# imu-pcb.net
KiCad netlist of a schematic drawn in Altium Designer
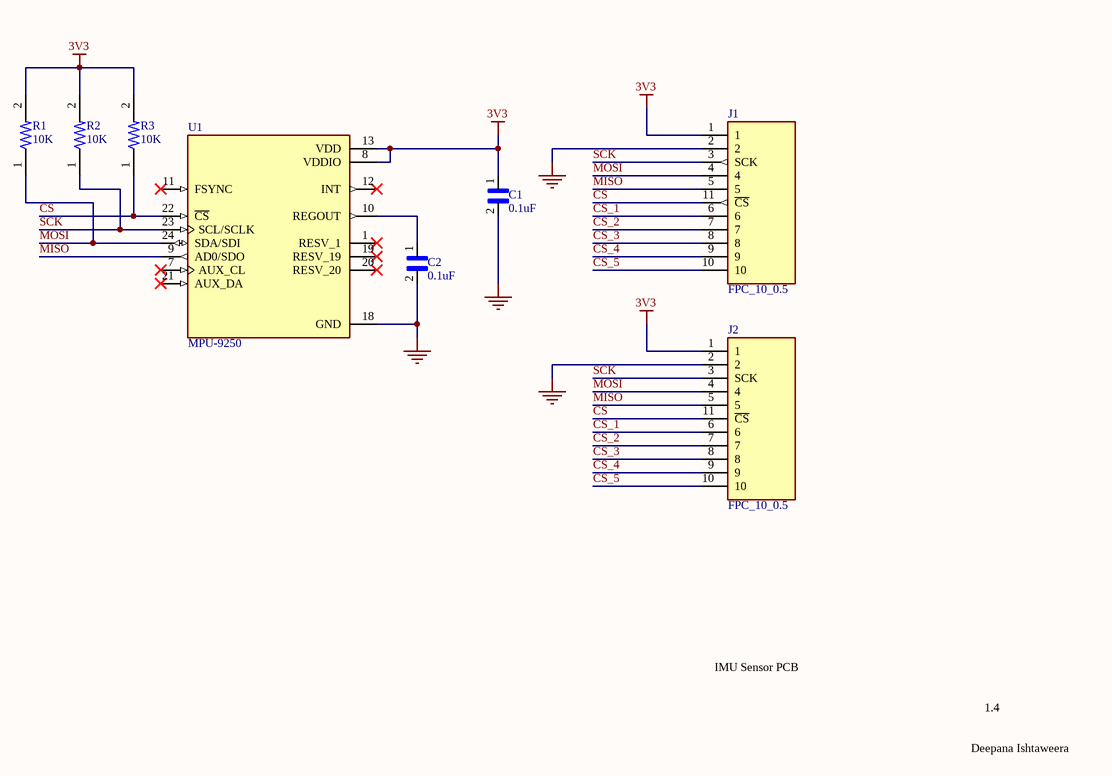
[diagram p0: imu-pcb.SchDoc]

(export (version "E")
  (design (tool "Eeschema 10.0.6"))
  (components
    (comp (ref "C1")
      (value "0.1uF")
      (footprint "CAPC1608X87N")
      (description "10000pF Â±10% 50V Ceramic Capacitor X7R 0603 (1608 Metric)")
      (fields (field (name "MF") "Walsin Technology") (field (name "MP") "0603B103K500CT"))
      (libsource (lib "imu-pcb-lib") (part "0603B103K500CT"))
    )
    (comp (ref "C2")
      (value "0.1uF")
      (footprint "CAPC1608X87N")
      (description "10000pF Â±10% 50V Ceramic Capacitor X7R 0603 (1608 Metric)")
      (fields (field (name "MF") "Walsin Technology") (field (name "MP") "0603B103K500CT"))
      (libsource (lib "imu-pcb-lib") (part "0603B103K500CT"))
    )
    (comp (ref "J1")
      (value "FPC_10_0.5")
      (footprint "FPC_10_0.5")
      (description "6 Position FPC Connector Contacts, Bottom 0.020 (0.50mm) Surface Mount, Right Angle")
      (fields (field (name "MP") "1734592-6") (field (name "MF") "TE Connectivity"))
      (libsource (lib "imu-pcb-lib") (part "FPC_10_0.5"))
    )
    (comp (ref "J2")
      (value "FPC_10_0.5")
      (footprint "FPC_10_0.5_1")
      (description "6 Position FPC Connector Contacts, Bottom 0.020 (0.50mm) Surface Mount, Right Angle")
      (fields (field (name "MP") "1734592-6") (field (name "MF") "TE Connectivity"))
      (libsource (lib "imu-pcb-lib") (part "FPC_10_0.5_1"))
    )
    (comp (ref "R1")
      (value "10K")
      (footprint "RESC1608X50N")
      (description "RES SMD 10 OHM 0.1% 1/16W 0603")
      (fields (field (name "MF") "TE Connectivity") (field (name "MP") "8-1614350-7"))
      (libsource (lib "imu-pcb-lib") (part "RES-0603"))
    )
    (comp (ref "R2")
      (value "10K")
      (footprint "RESC1608X50N")
      (description "RES SMD 10 OHM 0.1% 1/16W 0603")
      (fields (field (name "MF") "TE Connectivity") (field (name "MP") "8-1614350-7"))
      (libsource (lib "imu-pcb-lib") (part "RES-0603"))
    )
    (comp (ref "R3")
      (value "10K")
      (footprint "RESC1608X50N")
      (description "RES SMD 10 OHM 0.1% 1/16W 0603")
      (fields (field (name "MF") "TE Connectivity") (field (name "MP") "8-1614350-7"))
      (libsource (lib "imu-pcb-lib") (part "RES-0603"))
    )
    (comp (ref "U1")
      (value "MPU-9250")
      (footprint "QFN40P300X300X105-24N")
      (description "Accelerometer, Gyroscope, Magnetometer, 9 Axis Sensor IÂ²C, SPI Output")
      (fields (field (name "MF") "TDK InvenSense"))
      (libsource (lib "imu-pcb-lib") (part "MPU-9250"))
    )
  )
  (nets
    (net (code "1") (name "/CS") (class "Default")
      (node (ref "J1") (pin "11") (pinfunction "~{CS}_11") (pintype "output"))
      (node (ref "J2") (pin "11") (pinfunction "~{CS}_11") (pintype "passive"))
      (node (ref "R3") (pin "1") (pinfunction "1_1") (pintype "passive"))
      (node (ref "U1") (pin "22") (pinfunction "~{CS}_22") (pintype "input"))
    )
    (net (code "2") (name "/CS_1") (class "Default")
      (node (ref "J1") (pin "6") (pinfunction "6_6") (pintype "passive"))
      (node (ref "J2") (pin "6") (pinfunction "6_6") (pintype "passive"))
    )
    (net (code "3") (name "/CS_2") (class "Default")
      (node (ref "J1") (pin "7") (pinfunction "7_7") (pintype "passive"))
      (node (ref "J2") (pin "7") (pinfunction "7_7") (pintype "passive"))
    )
    (net (code "4") (name "/CS_3") (class "Default")
      (node (ref "J1") (pin "8") (pinfunction "8_8") (pintype "passive"))
      (node (ref "J2") (pin "8") (pinfunction "8_8") (pintype "passive"))
    )
    (net (code "5") (name "/CS_4") (class "Default")
      (node (ref "J1") (pin "9") (pinfunction "9_9") (pintype "passive"))
      (node (ref "J2") (pin "9") (pinfunction "9_9") (pintype "passive"))
    )
    (net (code "6") (name "/CS_5") (class "Default")
      (node (ref "J1") (pin "10") (pinfunction "10_10") (pintype "passive"))
      (node (ref "J2") (pin "10") (pinfunction "10_10") (pintype "passive"))
    )
    (net (code "7") (name "/MISO") (class "Default")
      (node (ref "J1") (pin "5") (pinfunction "5_5") (pintype "passive"))
      (node (ref "J2") (pin "5") (pinfunction "5_5") (pintype "passive"))
      (node (ref "U1") (pin "9") (pinfunction "AD0/SDO_9") (pintype "output"))
    )
    (net (code "8") (name "/MOSI") (class "Default")
      (node (ref "J1") (pin "4") (pinfunction "4_4") (pintype "passive"))
      (node (ref "J2") (pin "4") (pinfunction "4_4") (pintype "passive"))
      (node (ref "R1") (pin "1") (pinfunction "1_1") (pintype "passive"))
      (node (ref "U1") (pin "24") (pinfunction "SDA/SDI_24") (pintype "bidirectional"))
    )
    (net (code "9") (name "/SCK") (class "Default")
      (node (ref "J1") (pin "3") (pinfunction "SCK_3") (pintype "output"))
      (node (ref "J2") (pin "3") (pinfunction "SCK_3") (pintype "passive"))
      (node (ref "R2") (pin "1") (pinfunction "1_1") (pintype "passive"))
      (node (ref "U1") (pin "23") (pinfunction "SCL/SCLK_23") (pintype "input"))
    )
    (net (code "10") (name "3V3") (class "Default")
      (node (ref "C1") (pin "1") (pinfunction "1_1") (pintype "passive"))
      (node (ref "J1") (pin "1") (pinfunction "1_1") (pintype "passive"))
      (node (ref "J2") (pin "1") (pinfunction "1_1") (pintype "passive"))
      (node (ref "R1") (pin "2") (pinfunction "2_2") (pintype "passive"))
      (node (ref "R2") (pin "2") (pinfunction "2_2") (pintype "passive"))
      (node (ref "R3") (pin "2") (pinfunction "2_2") (pintype "passive"))
      (node (ref "U1") (pin "13") (pinfunction "VDD_13") (pintype "power_in"))
      (node (ref "U1") (pin "8") (pinfunction "VDDIO_8") (pintype "power_in"))
    )
    (net (code "11") (name "GND") (class "Default")
      (node (ref "C1") (pin "2") (pinfunction "2_2") (pintype "passive"))
      (node (ref "C2") (pin "2") (pinfunction "2_2") (pintype "passive"))
      (node (ref "J1") (pin "2") (pinfunction "2_2") (pintype "passive"))
      (node (ref "J2") (pin "2") (pinfunction "2_2") (pintype "passive"))
      (node (ref "U1") (pin "18") (pinfunction "GND_18") (pintype "power_in"))
    )
    (net (code "12") (name "Net-(U1-REGOUT)") (class "Default")
      (node (ref "C2") (pin "1") (pinfunction "1_1") (pintype "passive"))
      (node (ref "U1") (pin "10") (pinfunction "REGOUT_10") (pintype "output"))
    )
    (net (code "13") (name "unconnected-(U1-AUX_CL-Pad7)") (class "Default")
      (node (ref "U1") (pin "7") (pinfunction "AUX_CL_7") (pintype "input+no_connect"))
    )
    (net (code "14") (name "unconnected-(U1-AUX_DA-Pad21)") (class "Default")
      (node (ref "U1") (pin "21") (pinfunction "AUX_DA_21") (pintype "input+no_connect"))
    )
    (net (code "15") (name "unconnected-(U1-FSYNC-Pad11)") (class "Default")
      (node (ref "U1") (pin "11") (pinfunction "FSYNC_11") (pintype "input+no_connect"))
    )
    (net (code "16") (name "unconnected-(U1-INT-Pad12)") (class "Default")
      (node (ref "U1") (pin "12") (pinfunction "INT_12") (pintype "output+no_connect"))
    )
    (net (code "17") (name "unconnected-(U1-RESV_1-Pad1)") (class "Default")
      (node (ref "U1") (pin "1") (pinfunction "RESV_1_1") (pintype "passive+no_connect"))
    )
    (net (code "18") (name "unconnected-(U1-RESV_19-Pad19)") (class "Default")
      (node (ref "U1") (pin "19") (pinfunction "RESV_19_19") (pintype "passive+no_connect"))
    )
    (net (code "19") (name "unconnected-(U1-RESV_20-Pad20)") (class "Default")
      (node (ref "U1") (pin "20") (pinfunction "RESV_20_20") (pintype "passive+no_connect"))
    )
  )
)
